# STM32_Rauch_002.net
KiCad netlist of a schematic drawn in EAGLE
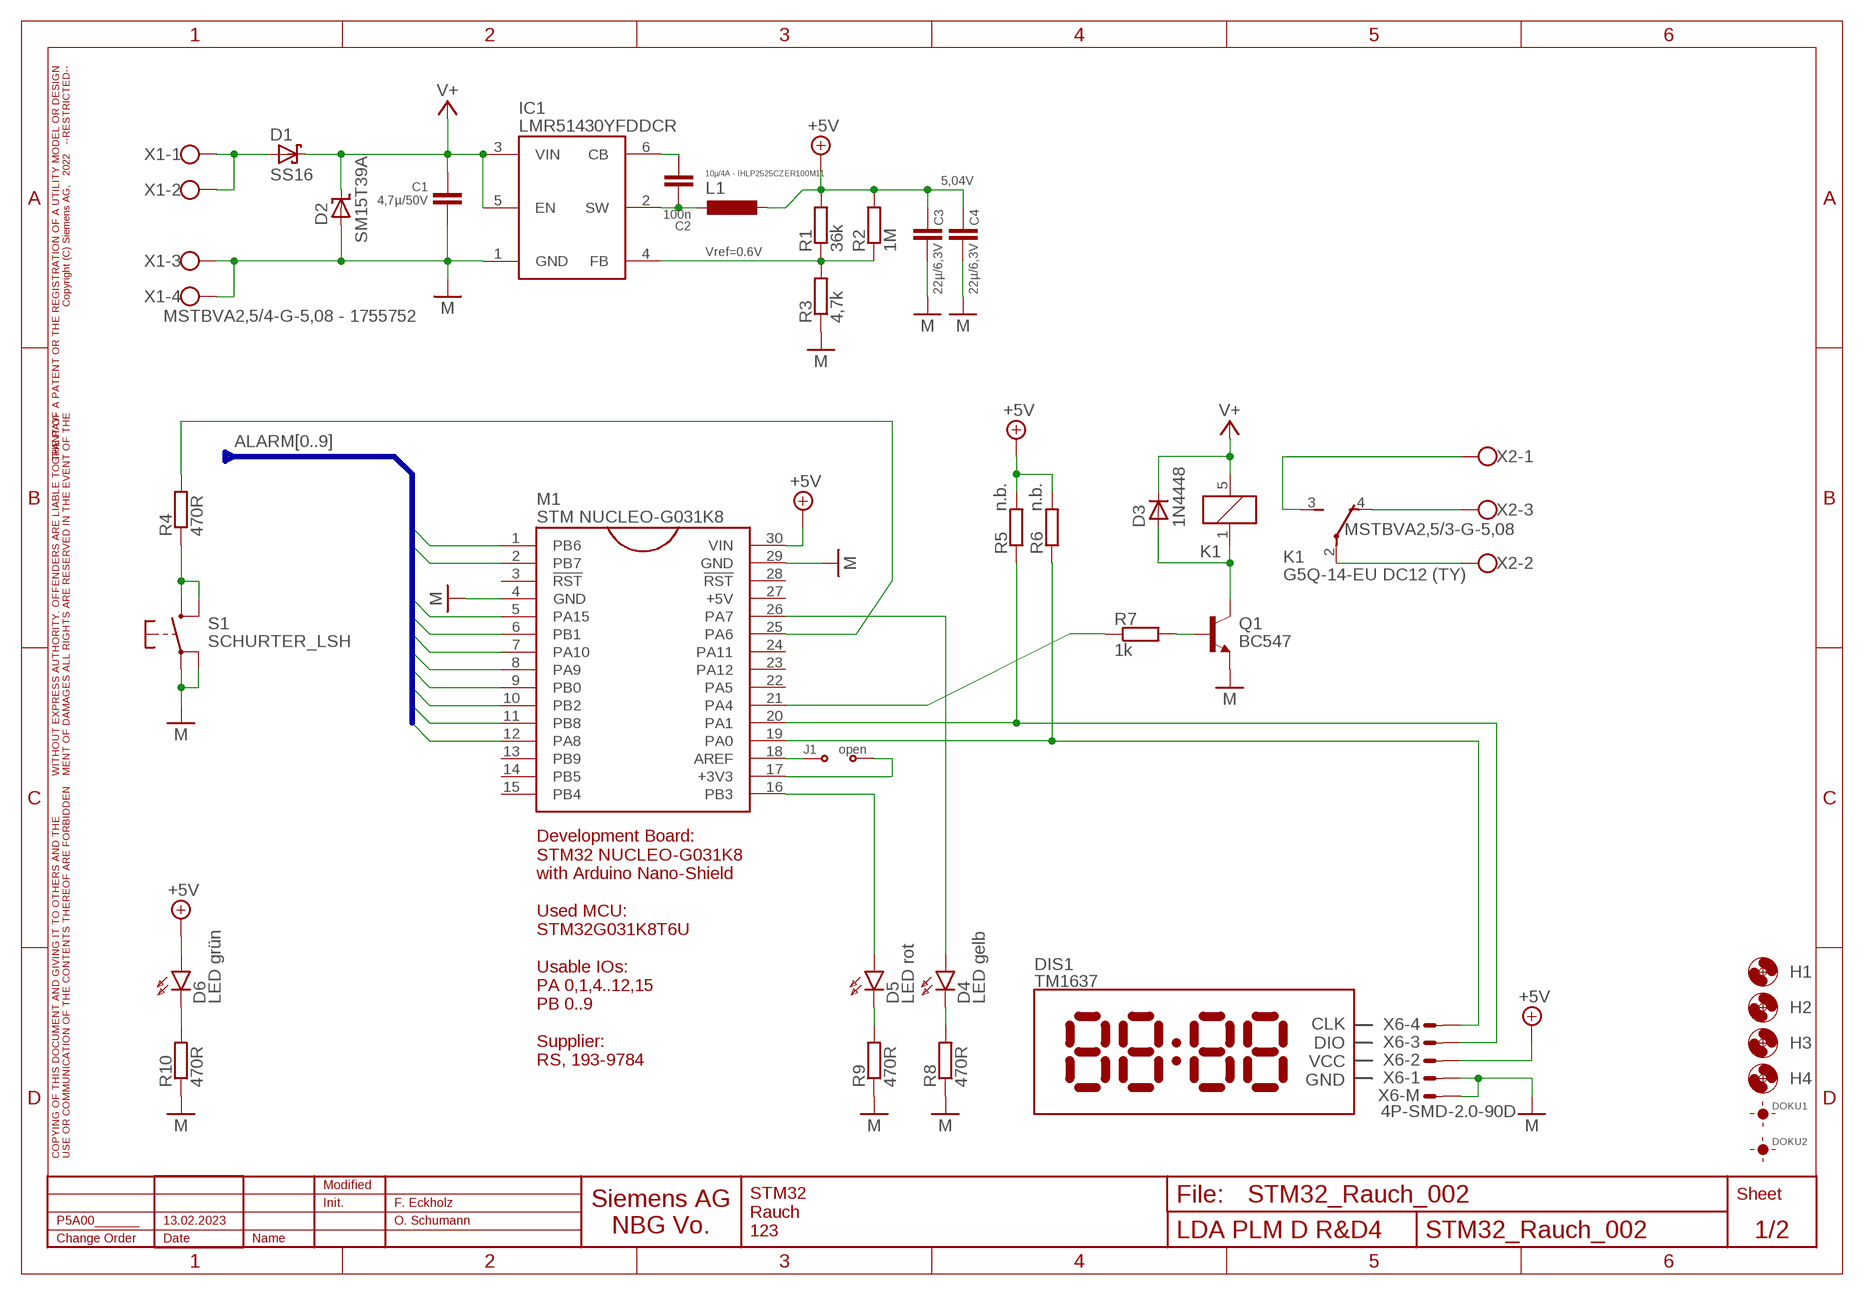
[diagram p0: schematic, sheet 1]
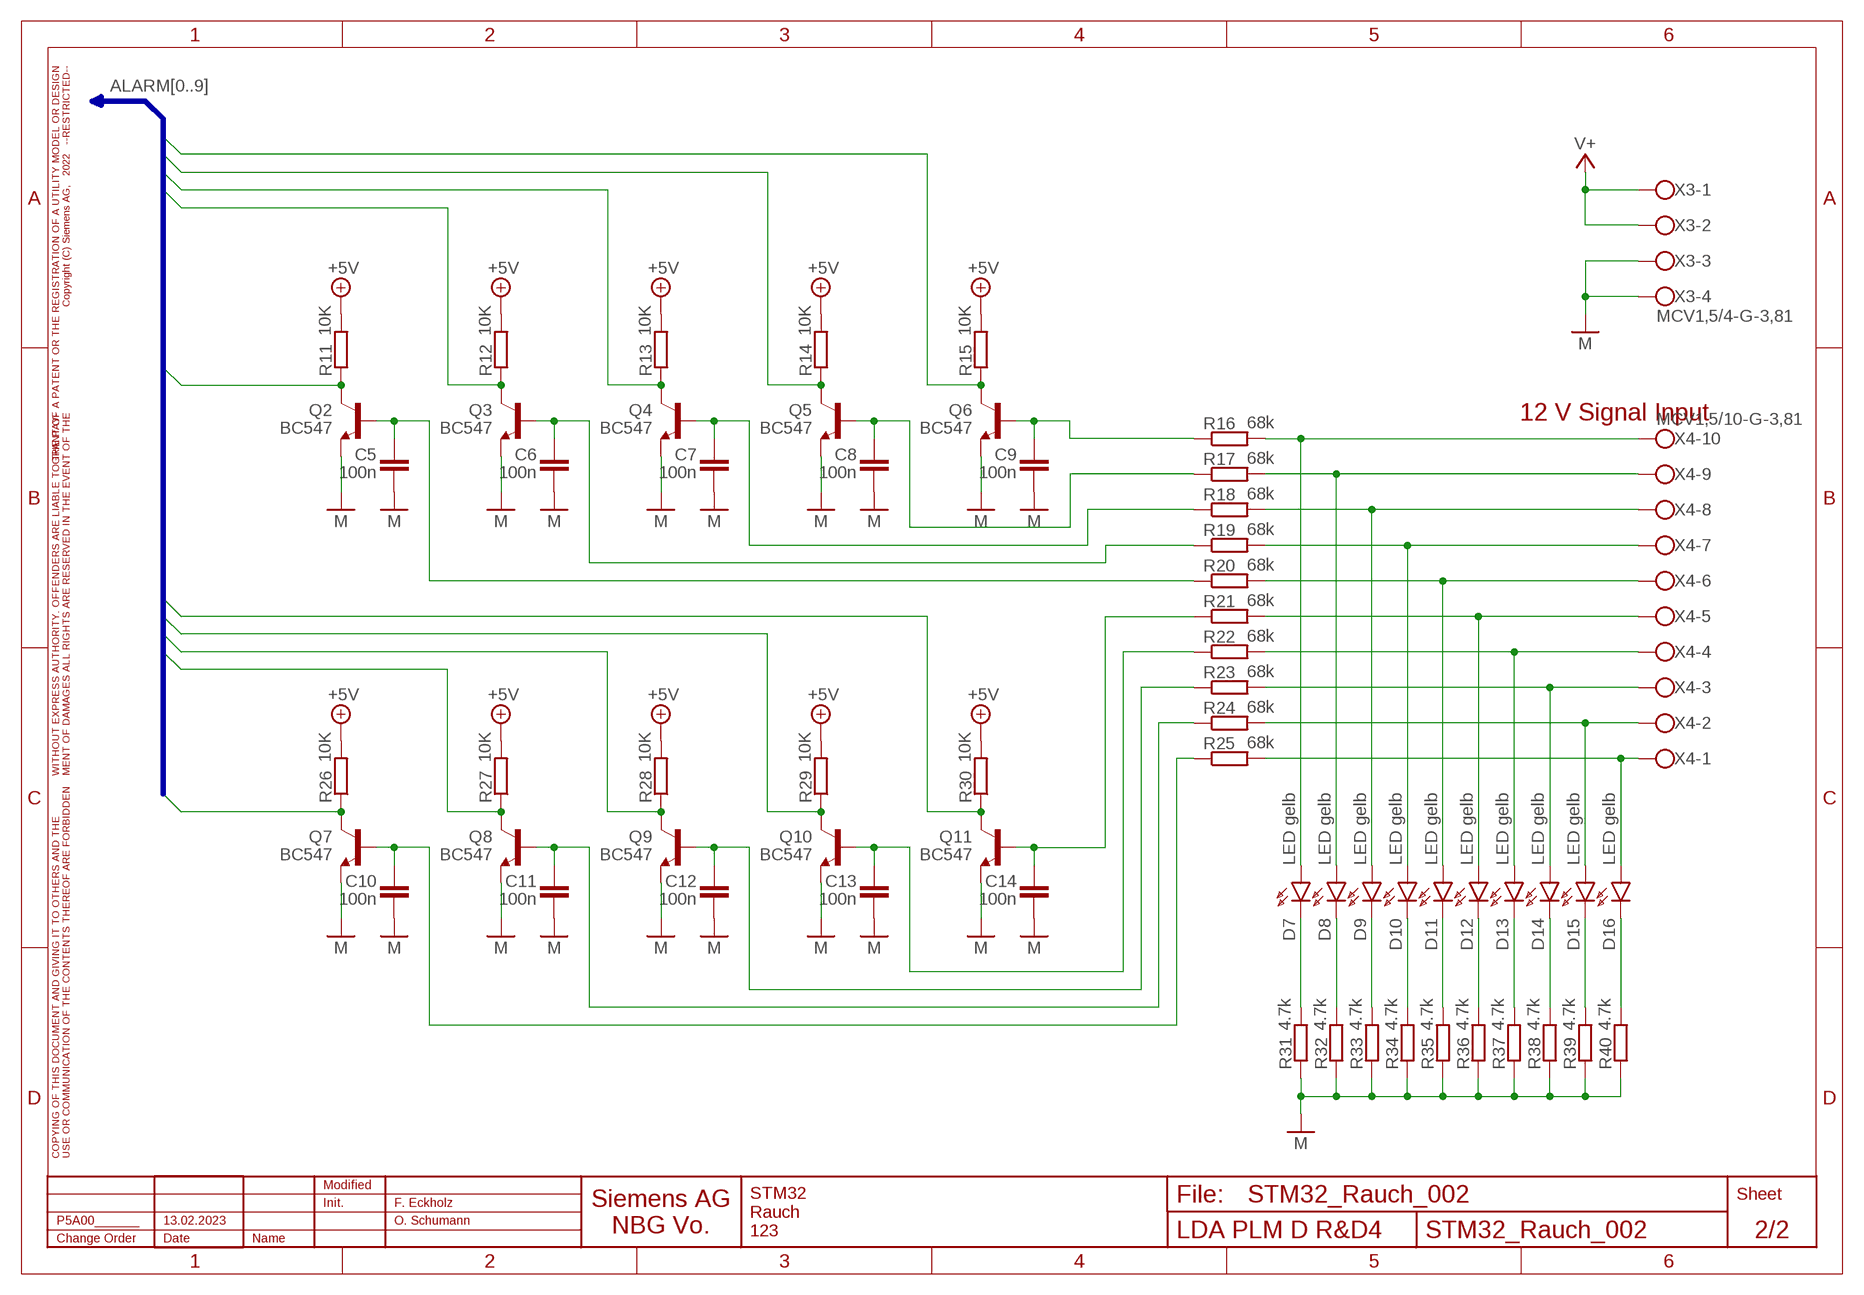
[diagram p1: schematic, sheet 2]

(export (version "E")
  (design (tool "Eeschema 10.0.6"))
  (components
    (comp (ref "C1")
      (value "4,7µ/50V")
      (footprint "eagle-import:CAPC1210")
      (libsource (lib "eagle-import") (part "C-EU1210"))
    )
    (comp (ref "C2")
      (value "100n")
      (footprint "eagle-import:CAPC0603")
      (libsource (lib "eagle-import") (part "C-EU0603"))
    )
    (comp (ref "C3")
      (value "22µ/6,3V")
      (footprint "eagle-import:CAPC1206")
      (libsource (lib "eagle-import") (part "C-EU1206"))
    )
    (comp (ref "C4")
      (value "22µ/6,3V")
      (footprint "eagle-import:CAPC1206")
      (libsource (lib "eagle-import") (part "C-EU1206"))
    )
    (comp (ref "D1")
      (value "SS16")
      (footprint "eagle-import:DIOM-SMA")
      (libsource (lib "eagle-import") (part "DIODE-SCHOTTKY-SMA"))
    )
    (comp (ref "D2")
      (value "SM15T39A")
      (footprint "eagle-import:DIOM-SMC")
      (libsource (lib "eagle-import") (part "DIODE-TVS-UNI-SMC"))
    )
    (comp (ref "D3")
      (value "1N4448")
      (footprint "eagle-import:SOD323")
      (libsource (lib "eagle-import") (part "DIODE-SOD323"))
    )
    (comp (ref "D4")
      (value "LED gelb")
      (footprint "eagle-import:LEDC1608")
      (libsource (lib "eagle-import") (part "DIODE-LED-C1608"))
    )
    (comp (ref "D5")
      (value "LED rot")
      (footprint "eagle-import:LEDC1608")
      (libsource (lib "eagle-import") (part "DIODE-LED-C1608"))
    )
    (comp (ref "D6")
      (value "LED grün")
      (footprint "eagle-import:LEDC1608")
      (libsource (lib "eagle-import") (part "DIODE-LED-C1608"))
    )
    (comp (ref "DIS1")
      (value "TM1637")
      (footprint "eagle-import:TM1637")
      (libsource (lib "eagle-import") (part "TM1637"))
    )
    (comp (ref "DOKU1")
      (value "PAD-FIDU-R200")
      (footprint "eagle-import:FIDU_RUND-2MM")
      (libsource (lib "eagle-import") (part "PAD-FIDU-R200"))
    )
    (comp (ref "DOKU2")
      (value "PAD-FIDU-R200")
      (footprint "eagle-import:FIDU_RUND-2MM")
      (libsource (lib "eagle-import") (part "PAD-FIDU-R200"))
    )
    (comp (ref "DOKU4")
      (value "STM32_Rauch_002")
      (footprint "eagle-import:DOKU-50-TOP")
      (libsource (lib "eagle-import") (part "TEXT-50-TOP"))
    )
    (comp (ref "H1")
      (value "MOUNT-HOLE-3.2")
      (footprint "eagle-import:MOUNT-HOLE-3,2")
      (libsource (lib "eagle-import") (part "MOUNT-HOLE-3.2"))
    )
    (comp (ref "H2")
      (value "MOUNT-HOLE-3.2")
      (footprint "eagle-import:MOUNT-HOLE-3,2")
      (libsource (lib "eagle-import") (part "MOUNT-HOLE-3.2"))
    )
    (comp (ref "H3")
      (value "MOUNT-HOLE-3.2")
      (footprint "eagle-import:MOUNT-HOLE-3,2")
      (libsource (lib "eagle-import") (part "MOUNT-HOLE-3.2"))
    )
    (comp (ref "H4")
      (value "MOUNT-HOLE-3.2")
      (footprint "eagle-import:MOUNT-HOLE-3,2")
      (libsource (lib "eagle-import") (part "MOUNT-HOLE-3.2"))
    )
    (comp (ref "IC1")
      (value "LMR51430YFDDCR")
      (footprint "eagle-import:SOT23-6")
      (libsource (lib "eagle-import") (part "LMR51430"))
    )
    (comp (ref "J1")
      (value "open")
      (footprint "eagle-import:CON-SOLDERJUMPER")
      (libsource (lib "eagle-import") (part "CON-J2D"))
    )
    (comp (ref "K1")
      (value "G5Q-14-EU DC12 (TY)")
      (footprint "eagle-import:OMRON-G5Q")
      (libsource (lib "eagle-import") (part "RELAIS1-OMRON-G5Q"))
    )
    (comp (ref "L1")
      (value "10µ/4A - IHLP2525CZER100M11")
      (footprint "eagle-import:INDM0707")
      (libsource (lib "eagle-import") (part "L-EU0707"))
    )
    (comp (ref "M1")
      (value "STM NUCLEO-G031K8")
      (footprint "eagle-import:NUCLEO32")
      (libsource (lib "eagle-import") (part "STM32-NUCLEO32"))
    )
    (comp (ref "Q1")
      (value "BC547")
      (footprint "eagle-import:SOT23")
      (libsource (lib "eagle-import") (part "TRANSISTOR-NPN-SOT23"))
    )
    (comp (ref "R1")
      (value "36k")
      (footprint "eagle-import:RESC0603")
      (libsource (lib "eagle-import") (part "R-EU_0603"))
    )
    (comp (ref "R2")
      (value "1M")
      (footprint "eagle-import:RESC0603")
      (libsource (lib "eagle-import") (part "R-EU_0603"))
    )
    (comp (ref "R3")
      (value "4,7k")
      (footprint "eagle-import:RESC0603")
      (libsource (lib "eagle-import") (part "R-EU_0603"))
    )
    (comp (ref "R4")
      (value "470R")
      (footprint "eagle-import:RESC0603")
      (libsource (lib "eagle-import") (part "R-EU_0603"))
    )
    (comp (ref "R5")
      (value "n.b.")
      (footprint "eagle-import:RESC0603")
      (libsource (lib "eagle-import") (part "R-EU_0603"))
    )
    (comp (ref "R6")
      (value "n.b.")
      (footprint "eagle-import:RESC0603")
      (libsource (lib "eagle-import") (part "R-EU_0603"))
    )
    (comp (ref "R7")
      (value "1k")
      (footprint "eagle-import:RESC0603")
      (libsource (lib "eagle-import") (part "R-EU_0603"))
    )
    (comp (ref "R8")
      (value "470R")
      (footprint "eagle-import:RESC0603")
      (libsource (lib "eagle-import") (part "R-EU_0603"))
    )
    (comp (ref "R9")
      (value "470R")
      (footprint "eagle-import:RESC0603")
      (libsource (lib "eagle-import") (part "R-EU_0603"))
    )
    (comp (ref "R10")
      (value "470R")
      (footprint "eagle-import:RESC0603")
      (libsource (lib "eagle-import") (part "R-EU_0603"))
    )
    (comp (ref "S1")
      (value "SCHURTER_LSH")
      (footprint "eagle-import:SHURTER_LSH")
      (libsource (lib "eagle-import") (part "SCHURTER_LSH"))
    )
    (comp (ref "X1")
      (value "MSTBVA2,5/4-G-5,08 - 1755752")
      (footprint "eagle-import:MSTBVA2,5_4-G-5,08")
      (libsource (lib "eagle-import") (part "MSTBVA2,5/4-G-5,08"))
    )
    (comp (ref "X2")
      (value "MSTBVA2,5/3-G-5,08")
      (footprint "eagle-import:MSTBVA2,5_3-G-5,08")
      (libsource (lib "eagle-import") (part "MSTBVA2,5/3-G-5,08"))
    )
    (comp (ref "X6")
      (value "4P-SMD-2.0-90D")
      (footprint "eagle-import:4P-SMD-2.0-90D")
      (libsource (lib "eagle-import") (part "4P-SMD-2.0-90D"))
    )
    (comp (ref "C5")
      (value "100n")
      (footprint "eagle-import:CAPC0603")
      (libsource (lib "eagle-import") (part "C-EU0603"))
    )
    (comp (ref "C6")
      (value "100n")
      (footprint "eagle-import:CAPC0603")
      (libsource (lib "eagle-import") (part "C-EU0603"))
    )
    (comp (ref "C7")
      (value "100n")
      (footprint "eagle-import:CAPC0603")
      (libsource (lib "eagle-import") (part "C-EU0603"))
    )
    (comp (ref "C8")
      (value "100n")
      (footprint "eagle-import:CAPC0603")
      (libsource (lib "eagle-import") (part "C-EU0603"))
    )
    (comp (ref "C9")
      (value "100n")
      (footprint "eagle-import:CAPC0603")
      (libsource (lib "eagle-import") (part "C-EU0603"))
    )
    (comp (ref "C10")
      (value "100n")
      (footprint "eagle-import:CAPC0603")
      (libsource (lib "eagle-import") (part "C-EU0603"))
    )
    (comp (ref "C11")
      (value "100n")
      (footprint "eagle-import:CAPC0603")
      (libsource (lib "eagle-import") (part "C-EU0603"))
    )
    (comp (ref "C12")
      (value "100n")
      (footprint "eagle-import:CAPC0603")
      (libsource (lib "eagle-import") (part "C-EU0603"))
    )
    (comp (ref "C13")
      (value "100n")
      (footprint "eagle-import:CAPC0603")
      (libsource (lib "eagle-import") (part "C-EU0603"))
    )
    (comp (ref "C14")
      (value "100n")
      (footprint "eagle-import:CAPC0603")
      (libsource (lib "eagle-import") (part "C-EU0603"))
    )
    (comp (ref "D7")
      (value "LED gelb")
      (footprint "eagle-import:LEDC1608")
      (libsource (lib "eagle-import") (part "DIODE-LED-C1608"))
    )
    (comp (ref "D8")
      (value "LED gelb")
      (footprint "eagle-import:LEDC1608")
      (libsource (lib "eagle-import") (part "DIODE-LED-C1608"))
    )
    (comp (ref "D9")
      (value "LED gelb")
      (footprint "eagle-import:LEDC1608")
      (libsource (lib "eagle-import") (part "DIODE-LED-C1608"))
    )
    (comp (ref "D10")
      (value "LED gelb")
      (footprint "eagle-import:LEDC1608")
      (libsource (lib "eagle-import") (part "DIODE-LED-C1608"))
    )
    (comp (ref "D11")
      (value "LED gelb")
      (footprint "eagle-import:LEDC1608")
      (libsource (lib "eagle-import") (part "DIODE-LED-C1608"))
    )
    (comp (ref "D12")
      (value "LED gelb")
      (footprint "eagle-import:LEDC1608")
      (libsource (lib "eagle-import") (part "DIODE-LED-C1608"))
    )
    (comp (ref "D13")
      (value "LED gelb")
      (footprint "eagle-import:LEDC1608")
      (libsource (lib "eagle-import") (part "DIODE-LED-C1608"))
    )
    (comp (ref "D14")
      (value "LED gelb")
      (footprint "eagle-import:LEDC1608")
      (libsource (lib "eagle-import") (part "DIODE-LED-C1608"))
    )
    (comp (ref "D15")
      (value "LED gelb")
      (footprint "eagle-import:LEDC1608")
      (libsource (lib "eagle-import") (part "DIODE-LED-C1608"))
    )
    (comp (ref "D16")
      (value "LED gelb")
      (footprint "eagle-import:LEDC1608")
      (libsource (lib "eagle-import") (part "DIODE-LED-C1608"))
    )
    (comp (ref "DOKU4")
      (value "STM32_Rauch_002")
      (footprint "eagle-import:DOKU-50-TOP")
      (libsource (lib "eagle-import") (part "TEXT-50-TOP"))
    )
    (comp (ref "Q2")
      (value "BC547")
      (footprint "eagle-import:SOT23")
      (libsource (lib "eagle-import") (part "TRANSISTOR-NPN-SOT23"))
    )
    (comp (ref "Q3")
      (value "BC547")
      (footprint "eagle-import:SOT23")
      (libsource (lib "eagle-import") (part "TRANSISTOR-NPN-SOT23"))
    )
    (comp (ref "Q4")
      (value "BC547")
      (footprint "eagle-import:SOT23")
      (libsource (lib "eagle-import") (part "TRANSISTOR-NPN-SOT23"))
    )
    (comp (ref "Q5")
      (value "BC547")
      (footprint "eagle-import:SOT23")
      (libsource (lib "eagle-import") (part "TRANSISTOR-NPN-SOT23"))
    )
    (comp (ref "Q6")
      (value "BC547")
      (footprint "eagle-import:SOT23")
      (libsource (lib "eagle-import") (part "TRANSISTOR-NPN-SOT23"))
    )
    (comp (ref "Q7")
      (value "BC547")
      (footprint "eagle-import:SOT23")
      (libsource (lib "eagle-import") (part "TRANSISTOR-NPN-SOT23"))
    )
    (comp (ref "Q8")
      (value "BC547")
      (footprint "eagle-import:SOT23")
      (libsource (lib "eagle-import") (part "TRANSISTOR-NPN-SOT23"))
    )
    (comp (ref "Q9")
      (value "BC547")
      (footprint "eagle-import:SOT23")
      (libsource (lib "eagle-import") (part "TRANSISTOR-NPN-SOT23"))
    )
    (comp (ref "Q10")
      (value "BC547")
      (footprint "eagle-import:SOT23")
      (libsource (lib "eagle-import") (part "TRANSISTOR-NPN-SOT23"))
    )
    (comp (ref "Q11")
      (value "BC547")
      (footprint "eagle-import:SOT23")
      (libsource (lib "eagle-import") (part "TRANSISTOR-NPN-SOT23"))
    )
    (comp (ref "R11")
      (value "10K")
      (footprint "eagle-import:RESC0603")
      (libsource (lib "eagle-import") (part "R-EU_0603"))
    )
    (comp (ref "R12")
      (value "10K")
      (footprint "eagle-import:RESC0603")
      (libsource (lib "eagle-import") (part "R-EU_0603"))
    )
    (comp (ref "R13")
      (value "10K")
      (footprint "eagle-import:RESC0603")
      (libsource (lib "eagle-import") (part "R-EU_0603"))
    )
    (comp (ref "R14")
      (value "10K")
      (footprint "eagle-import:RESC0603")
      (libsource (lib "eagle-import") (part "R-EU_0603"))
    )
    (comp (ref "R15")
      (value "10K")
      (footprint "eagle-import:RESC0603")
      (libsource (lib "eagle-import") (part "R-EU_0603"))
    )
    (comp (ref "R16")
      (value "68k")
      (footprint "eagle-import:RESC0603")
      (libsource (lib "eagle-import") (part "R-EU_0603"))
    )
    (comp (ref "R17")
      (value "68k")
      (footprint "eagle-import:RESC0603")
      (libsource (lib "eagle-import") (part "R-EU_0603"))
    )
    (comp (ref "R18")
      (value "68k")
      (footprint "eagle-import:RESC0603")
      (libsource (lib "eagle-import") (part "R-EU_0603"))
    )
    (comp (ref "R19")
      (value "68k")
      (footprint "eagle-import:RESC0603")
      (libsource (lib "eagle-import") (part "R-EU_0603"))
    )
    (comp (ref "R20")
      (value "68k")
      (footprint "eagle-import:RESC0603")
      (libsource (lib "eagle-import") (part "R-EU_0603"))
    )
    (comp (ref "R21")
      (value "68k")
      (footprint "eagle-import:RESC0603")
      (libsource (lib "eagle-import") (part "R-EU_0603"))
    )
    (comp (ref "R22")
      (value "68k")
      (footprint "eagle-import:RESC0603")
      (libsource (lib "eagle-import") (part "R-EU_0603"))
    )
    (comp (ref "R23")
      (value "68k")
      (footprint "eagle-import:RESC0603")
      (libsource (lib "eagle-import") (part "R-EU_0603"))
    )
    (comp (ref "R24")
      (value "68k")
      (footprint "eagle-import:RESC0603")
      (libsource (lib "eagle-import") (part "R-EU_0603"))
    )
    (comp (ref "R25")
      (value "68k")
      (footprint "eagle-import:RESC0603")
      (libsource (lib "eagle-import") (part "R-EU_0603"))
    )
    (comp (ref "R26")
      (value "10K")
      (footprint "eagle-import:RESC0603")
      (libsource (lib "eagle-import") (part "R-EU_0603"))
    )
    (comp (ref "R27")
      (value "10K")
      (footprint "eagle-import:RESC0603")
      (libsource (lib "eagle-import") (part "R-EU_0603"))
    )
    (comp (ref "R28")
      (value "10K")
      (footprint "eagle-import:RESC0603")
      (libsource (lib "eagle-import") (part "R-EU_0603"))
    )
    (comp (ref "R29")
      (value "10K")
      (footprint "eagle-import:RESC0603")
      (libsource (lib "eagle-import") (part "R-EU_0603"))
    )
    (comp (ref "R30")
      (value "10K")
      (footprint "eagle-import:RESC0603")
      (libsource (lib "eagle-import") (part "R-EU_0603"))
    )
    (comp (ref "R31")
      (value "4.7k")
      (footprint "eagle-import:RESC0603")
      (libsource (lib "eagle-import") (part "R-EU_0603"))
    )
    (comp (ref "R32")
      (value "4.7k")
      (footprint "eagle-import:RESC0603")
      (libsource (lib "eagle-import") (part "R-EU_0603"))
    )
    (comp (ref "R33")
      (value "4.7k")
      (footprint "eagle-import:RESC0603")
      (libsource (lib "eagle-import") (part "R-EU_0603"))
    )
    (comp (ref "R34")
      (value "4.7k")
      (footprint "eagle-import:RESC0603")
      (libsource (lib "eagle-import") (part "R-EU_0603"))
    )
    (comp (ref "R35")
      (value "4.7k")
      (footprint "eagle-import:RESC0603")
      (libsource (lib "eagle-import") (part "R-EU_0603"))
    )
    (comp (ref "R36")
      (value "4.7k")
      (footprint "eagle-import:RESC0603")
      (libsource (lib "eagle-import") (part "R-EU_0603"))
    )
    (comp (ref "R37")
      (value "4.7k")
      (footprint "eagle-import:RESC0603")
      (libsource (lib "eagle-import") (part "R-EU_0603"))
    )
    (comp (ref "R38")
      (value "4.7k")
      (footprint "eagle-import:RESC0603")
      (libsource (lib "eagle-import") (part "R-EU_0603"))
    )
    (comp (ref "R39")
      (value "4.7k")
      (footprint "eagle-import:RESC0603")
      (libsource (lib "eagle-import") (part "R-EU_0603"))
    )
    (comp (ref "R40")
      (value "4.7k")
      (footprint "eagle-import:RESC0603")
      (libsource (lib "eagle-import") (part "R-EU_0603"))
    )
    (comp (ref "X3")
      (value "MCV1,5/4-G-3,81")
      (footprint "eagle-import:MCV1,5_4-G-3,81")
      (libsource (lib "eagle-import") (part "MCV1,5/4-G-3,81"))
    )
    (comp (ref "X4")
      (value "MCV1,5/10-G-3,81")
      (footprint "eagle-import:MCV1,5_10-G-3,81")
      (libsource (lib "eagle-import") (part "MCV1,5/10-G-3,81"))
    )
  )
  (nets
    (net (code "1") (name "+5V") (class "Default")
      (node (ref "C3") (pin "2") (pinfunction "2_2") (pintype "passive"))
      (node (ref "C4") (pin "2") (pinfunction "2_2") (pintype "passive"))
      (node (ref "D6") (pin "2") (pinfunction "A_2") (pintype "passive"))
      (node (ref "L1") (pin "2") (pinfunction "2_2") (pintype "passive"))
      (node (ref "M1") (pin "30") (pinfunction "VIN_30") (pintype "passive"))
      (node (ref "R1") (pin "2") (pinfunction "2_2") (pintype "passive"))
      (node (ref "R11") (pin "2") (pinfunction "2_2") (pintype "passive"))
      (node (ref "R12") (pin "2") (pinfunction "2_2") (pintype "passive"))
      (node (ref "R13") (pin "2") (pinfunction "2_2") (pintype "passive"))
      (node (ref "R14") (pin "2") (pinfunction "2_2") (pintype "passive"))
      (node (ref "R15") (pin "2") (pinfunction "2_2") (pintype "passive"))
      (node (ref "R2") (pin "2") (pinfunction "2_2") (pintype "passive"))
      (node (ref "R26") (pin "2") (pinfunction "2_2") (pintype "passive"))
      (node (ref "R27") (pin "2") (pinfunction "2_2") (pintype "passive"))
      (node (ref "R28") (pin "2") (pinfunction "2_2") (pintype "passive"))
      (node (ref "R29") (pin "2") (pinfunction "2_2") (pintype "passive"))
      (node (ref "R30") (pin "2") (pinfunction "2_2") (pintype "passive"))
      (node (ref "R5") (pin "2") (pinfunction "2_2") (pintype "passive"))
      (node (ref "R6") (pin "2") (pinfunction "2_2") (pintype "passive"))
      (node (ref "X6") (pin "2") (pinfunction "S_2") (pintype "passive"))
    )
    (net (code "4") (name "ALARM0") (class "Default")
      (node (ref "M1") (pin "1") (pinfunction "PB6_1") (pintype "bidirectional"))
      (node (ref "Q6") (pin "3") (pinfunction "C_3") (pintype "passive"))
      (node (ref "R15") (pin "1") (pinfunction "1_1") (pintype "passive"))
    )
    (net (code "5") (name "ALARM1") (class "Default")
      (node (ref "M1") (pin "2") (pinfunction "PB7_2") (pintype "bidirectional"))
      (node (ref "Q5") (pin "3") (pinfunction "C_3") (pintype "passive"))
      (node (ref "R14") (pin "1") (pinfunction "1_1") (pintype "passive"))
    )
    (net (code "6") (name "ALARM2") (class "Default")
      (node (ref "M1") (pin "5") (pinfunction "PA15_5") (pintype "bidirectional"))
      (node (ref "Q4") (pin "3") (pinfunction "C_3") (pintype "passive"))
      (node (ref "R13") (pin "1") (pinfunction "1_1") (pintype "passive"))
    )
    (net (code "7") (name "ALARM3") (class "Default")
      (node (ref "M1") (pin "6") (pinfunction "PB1_6") (pintype "bidirectional"))
      (node (ref "Q3") (pin "3") (pinfunction "C_3") (pintype "passive"))
      (node (ref "R12") (pin "1") (pinfunction "1_1") (pintype "passive"))
    )
    (net (code "8") (name "ALARM4") (class "Default")
      (node (ref "M1") (pin "7") (pinfunction "PA10_7") (pintype "bidirectional"))
      (node (ref "Q2") (pin "3") (pinfunction "C_3") (pintype "passive"))
      (node (ref "R11") (pin "1") (pinfunction "1_1") (pintype "passive"))
    )
    (net (code "9") (name "ALARM5") (class "Default")
      (node (ref "M1") (pin "8") (pinfunction "PA9_8") (pintype "bidirectional"))
      (node (ref "Q11") (pin "3") (pinfunction "C_3") (pintype "passive"))
      (node (ref "R30") (pin "1") (pinfunction "1_1") (pintype "passive"))
    )
    (net (code "10") (name "ALARM6") (class "Default")
      (node (ref "M1") (pin "9") (pinfunction "PB0_9") (pintype "bidirectional"))
      (node (ref "Q10") (pin "3") (pinfunction "C_3") (pintype "passive"))
      (node (ref "R29") (pin "1") (pinfunction "1_1") (pintype "passive"))
    )
    (net (code "11") (name "ALARM7") (class "Default")
      (node (ref "M1") (pin "10") (pinfunction "PB2_10") (pintype "bidirectional"))
      (node (ref "Q9") (pin "3") (pinfunction "C_3") (pintype "passive"))
      (node (ref "R28") (pin "1") (pinfunction "1_1") (pintype "passive"))
    )
    (net (code "12") (name "ALARM8") (class "Default")
      (node (ref "M1") (pin "11") (pinfunction "PB8_11") (pintype "bidirectional"))
      (node (ref "Q8") (pin "3") (pinfunction "C_3") (pintype "passive"))
      (node (ref "R27") (pin "1") (pinfunction "1_1") (pintype "passive"))
    )
    (net (code "13") (name "ALARM9") (class "Default")
      (node (ref "M1") (pin "12") (pinfunction "PA8_12") (pintype "bidirectional"))
      (node (ref "Q7") (pin "3") (pinfunction "C_3") (pintype "passive"))
      (node (ref "R26") (pin "1") (pinfunction "1_1") (pintype "passive"))
    )
    (net (code "14") (name "M") (class "Default")
      (node (ref "C1") (pin "1") (pinfunction "1_1") (pintype "passive"))
      (node (ref "C10") (pin "1") (pinfunction "1_1") (pintype "passive"))
      (node (ref "C11") (pin "1") (pinfunction "1_1") (pintype "passive"))
      (node (ref "C12") (pin "1") (pinfunction "1_1") (pintype "passive"))
      (node (ref "C13") (pin "1") (pinfunction "1_1") (pintype "passive"))
      (node (ref "C14") (pin "1") (pinfunction "1_1") (pintype "passive"))
      (node (ref "C3") (pin "1") (pinfunction "1_1") (pintype "passive"))
      (node (ref "C4") (pin "1") (pinfunction "1_1") (pintype "passive"))
      (node (ref "C5") (pin "1") (pinfunction "1_1") (pintype "passive"))
      (node (ref "C6") (pin "1") (pinfunction "1_1") (pintype "passive"))
      (node (ref "C7") (pin "1") (pinfunction "1_1") (pintype "passive"))
      (node (ref "C8") (pin "1") (pinfunction "1_1") (pintype "passive"))
      (node (ref "C9") (pin "1") (pinfunction "1_1") (pintype "passive"))
      (node (ref "D2") (pin "2") (pinfunction "A_2") (pintype "passive"))
      (node (ref "IC1") (pin "1") (pinfunction "GND_1") (pintype "power_in"))
      (node (ref "M1") (pin "29") (pinfunction "GND_29") (pintype "passive"))
      (node (ref "M1") (pin "4") (pinfunction "GND_4") (pintype "passive"))
      (node (ref "Q1") (pin "2") (pinfunction "E_2") (pintype "passive"))
      (node (ref "Q10") (pin "2") (pinfunction "E_2") (pintype "passive"))
      (node (ref "Q11") (pin "2") (pinfunction "E_2") (pintype "passive"))
      (node (ref "Q2") (pin "2") (pinfunction "E_2") (pintype "passive"))
      (node (ref "Q3") (pin "2") (pinfunction "E_2") (pintype "passive"))
      (node (ref "Q4") (pin "2") (pinfunction "E_2") (pintype "passive"))
      (node (ref "Q5") (pin "2") (pinfunction "E_2") (pintype "passive"))
      (node (ref "Q6") (pin "2") (pinfunction "E_2") (pintype "passive"))
      (node (ref "Q7") (pin "2") (pinfunction "E_2") (pintype "passive"))
      (node (ref "Q8") (pin "2") (pinfunction "E_2") (pintype "passive"))
      (node (ref "Q9") (pin "2") (pinfunction "E_2") (pintype "passive"))
      (node (ref "R10") (pin "1") (pinfunction "1_1") (pintype "passive"))
      (node (ref "R3") (pin "1") (pinfunction "1_1") (pintype "passive"))
      (node (ref "R31") (pin "1") (pinfunction "1_1") (pintype "passive"))
      (node (ref "R32") (pin "1") (pinfunction "1_1") (pintype "passive"))
      (node (ref "R33") (pin "1") (pinfunction "1_1") (pintype "passive"))
      (node (ref "R34") (pin "1") (pinfunction "1_1") (pintype "passive"))
      (node (ref "R35") (pin "1") (pinfunction "1_1") (pintype "passive"))
      (node (ref "R36") (pin "1") (pinfunction "1_1") (pintype "passive"))
      (node (ref "R37") (pin "1") (pinfunction "1_1") (pintype "passive"))
      (node (ref "R38") (pin "1") (pinfunction "1_1") (pintype "passive"))
      (node (ref "R39") (pin "1") (pinfunction "1_1") (pintype "passive"))
      (node (ref "R40") (pin "1") (pinfunction "1_1") (pintype "passive"))
      (node (ref "R8") (pin "1") (pinfunction "1_1") (pintype "passive"))
      (node (ref "R9") (pin "1") (pinfunction "1_1") (pintype "passive"))
      (node (ref "S1") (pin "1") (pinfunction "P_1") (pintype "passive"))
      (node (ref "S1") (pin "2") (pinfunction "P_2") (pintype "passive"))
      (node (ref "X1") (pin "3") (pinfunction "KL_3") (pintype "passive"))
      (node (ref "X1") (pin "4") (pinfunction "KL_4") (pintype "passive"))
      (node (ref "X3") (pin "P$3") (pinfunction "KL_P$3") (pintype "passive"))
      (node (ref "X3") (pin "P$4") (pinfunction "KL_P$4") (pintype "passive"))
      (node (ref "X6") (pin "1") (pinfunction "S_1") (pintype "passive"))
      (node (ref "X6") (pin "SS1") (pinfunction "S_SS1") (pintype "passive"))
      (node (ref "X6") (pin "SS2") (pinfunction "S_SS2") (pintype "passive"))
    )
    (net (code "15") (name "Net-(D1-A)") (class "Default")
      (node (ref "D1") (pin "2") (pinfunction "A_2") (pintype "passive"))
      (node (ref "X1") (pin "1") (pinfunction "KL_1") (pintype "passive"))
      (node (ref "X1") (pin "2") (pinfunction "KL_2") (pintype "passive"))
    )
    (net (code "16") (name "Net-(D4-A)") (class "Default")
      (node (ref "D4") (pin "2") (pinfunction "A_2") (pintype "passive"))
      (node (ref "M1") (pin "26") (pinfunction "PA7_26") (pintype "bidirectional"))
    )
    (net (code "17") (name "Net-(D4-C)") (class "Default")
      (node (ref "D4") (pin "1") (pinfunction "C_1") (pintype "passive"))
      (node (ref "R8") (pin "2") (pinfunction "2_2") (pintype "passive"))
    )
    (net (code "18") (name "Net-(D5-A)") (class "Default")
      (node (ref "D5") (pin "2") (pinfunction "A_2") (pintype "passive"))
      (node (ref "M1") (pin "16") (pinfunction "PB3_16") (pintype "bidirectional"))
    )
    (net (code "19") (name "Net-(D5-C)") (class "Default")
      (node (ref "D5") (pin "1") (pinfunction "C_1") (pintype "passive"))
      (node (ref "R9") (pin "2") (pinfunction "2_2") (pintype "passive"))
    )
    (net (code "20") (name "Net-(D6-C)") (class "Default")
      (node (ref "D6") (pin "1") (pinfunction "C_1") (pintype "passive"))
      (node (ref "R10") (pin "2") (pinfunction "2_2") (pintype "passive"))
    )
    (net (code "21") (name "Net-(D7-A)") (class "Default")
      (node (ref "D7") (pin "2") (pinfunction "A_2") (pintype "passive"))
      (node (ref "R16") (pin "2") (pinfunction "2_2") (pintype "passive"))
      (node (ref "X4") (pin "P$10") (pinfunction "KL_P$10") (pintype "passive"))
    )
    (net (code "22") (name "Net-(D7-C)") (class "Default")
      (node (ref "D7") (pin "1") (pinfunction "C_1") (pintype "passive"))
      (node (ref "R31") (pin "2") (pinfunction "2_2") (pintype "passive"))
    )
    (net (code "23") (name "Net-(D8-A)") (class "Default")
      (node (ref "D8") (pin "2") (pinfunction "A_2") (pintype "passive"))
      (node (ref "R17") (pin "2") (pinfunction "2_2") (pintype "passive"))
      (node (ref "X4") (pin "P$9") (pinfunction "KL_P$9") (pintype "passive"))
    )
    (net (code "24") (name "Net-(D8-C)") (class "Default")
      (node (ref "D8") (pin "1") (pinfunction "C_1") (pintype "passive"))
      (node (ref "R32") (pin "2") (pinfunction "2_2") (pintype "passive"))
    )
    (net (code "25") (name "Net-(D9-A)") (class "Default")
      (node (ref "D9") (pin "2") (pinfunction "A_2") (pintype "passive"))
      (node (ref "R18") (pin "2") (pinfunction "2_2") (pintype "passive"))
      (node (ref "X4") (pin "P$8") (pinfunction "KL_P$8") (pintype "passive"))
    )
    (net (code "26") (name "Net-(D9-C)") (class "Default")
      (node (ref "D9") (pin "1") (pinfunction "C_1") (pintype "passive"))
      (node (ref "R33") (pin "2") (pinfunction "2_2") (pintype "passive"))
    )
    (net (code "27") (name "Net-(D10-A)") (class "Default")
      (node (ref "D10") (pin "2") (pinfunction "A_2") (pintype "passive"))
      (node (ref "R19") (pin "2") (pinfunction "2_2") (pintype "passive"))
      (node (ref "X4") (pin "P$7") (pinfunction "KL_P$7") (pintype "passive"))
    )
    (net (code "28") (name "Net-(D10-C)") (class "Default")
      (node (ref "D10") (pin "1") (pinfunction "C_1") (pintype "passive"))
      (node (ref "R34") (pin "2") (pinfunction "2_2") (pintype "passive"))
    )
    (net (code "29") (name "Net-(D11-A)") (class "Default")
      (node (ref "D11") (pin "2") (pinfunction "A_2") (pintype "passive"))
      (node (ref "R20") (pin "2") (pinfunction "2_2") (pintype "passive"))
      (node (ref "X4") (pin "P$6") (pinfunction "KL_P$6") (pintype "passive"))
    )
    (net (code "30") (name "Net-(D11-C)") (class "Default")
      (node (ref "D11") (pin "1") (pinfunction "C_1") (pintype "passive"))
      (node (ref "R35") (pin "2") (pinfunction "2_2") (pintype "passive"))
    )
    (net (code "31") (name "Net-(D12-A)") (class "Default")
      (node (ref "D12") (pin "2") (pinfunction "A_2") (pintype "passive"))
      (node (ref "R21") (pin "2") (pinfunction "2_2") (pintype "passive"))
      (node (ref "X4") (pin "P$5") (pinfunction "KL_P$5") (pintype "passive"))
    )
    (net (code "32") (name "Net-(D12-C)") (class "Default")
      (node (ref "D12") (pin "1") (pinfunction "C_1") (pintype "passive"))
      (node (ref "R36") (pin "2") (pinfunction "2_2") (pintype "passive"))
    )
    (net (code "33") (name "Net-(D13-A)") (class "Default")
      (node (ref "D13") (pin "2") (pinfunction "A_2") (pintype "passive"))
      (node (ref "R22") (pin "2") (pinfunction "2_2") (pintype "passive"))
      (node (ref "X4") (pin "P$4") (pinfunction "KL_P$4") (pintype "passive"))
    )
    (net (code "34") (name "Net-(D13-C)") (class "Default")
      (node (ref "D13") (pin "1") (pinfunction "C_1") (pintype "passive"))
      (node (ref "R37") (pin "2") (pinfunction "2_2") (pintype "passive"))
    )
    (net (code "35") (name "Net-(D14-A)") (class "Default")
      (node (ref "D14") (pin "2") (pinfunction "A_2") (pintype "passive"))
      (node (ref "R23") (pin "2") (pinfunction "2_2") (pintype "passive"))
      (node (ref "X4") (pin "P$3") (pinfunction "KL_P$3") (pintype "passive"))
    )
    (net (code "36") (name "Net-(D14-C)") (class "Default")
      (node (ref "D14") (pin "1") (pinfunction "C_1") (pintype "passive"))
      (node (ref "R38") (pin "2") (pinfunction "2_2") (pintype "passive"))
    )
    (net (code "37") (name "Net-(D15-A)") (class "Default")
      (node (ref "D15") (pin "2") (pinfunction "A_2") (pintype "passive"))
      (node (ref "R24") (pin "2") (pinfunction "2_2") (pintype "passive"))
      (node (ref "X4") (pin "P$2") (pinfunction "KL_P$2") (pintype "passive"))
    )
    (net (code "38") (name "Net-(D15-C)") (class "Default")
      (node (ref "D15") (pin "1") (pinfunction "C_1") (pintype "passive"))
      (node (ref "R39") (pin "2") (pinfunction "2_2") (pintype "passive"))
    )
    (net (code "39") (name "Net-(D16-A)") (class "Default")
      (node (ref "D16") (pin "2") (pinfunction "A_2") (pintype "passive"))
      (node (ref "R25") (pin "2") (pinfunction "2_2") (pintype "passive"))
      (node (ref "X4") (pin "P$1") (pinfunction "KL_P$1") (pintype "passive"))
    )
    (net (code "40") (name "Net-(D16-C)") (class "Default")
      (node (ref "D16") (pin "1") (pinfunction "C_1") (pintype "passive"))
      (node (ref "R40") (pin "2") (pinfunction "2_2") (pintype "passive"))
    )
    (net (code "41") (name "Net-(IC1-CB)") (class "Default")
      (node (ref "C2") (pin "1") (pinfunction "1_1") (pintype "passive"))
      (node (ref "IC1") (pin "6") (pinfunction "CB_6") (pintype "input"))
    )
    (net (code "42") (name "Net-(IC1-FB)") (class "Default")
      (node (ref "IC1") (pin "4") (pinfunction "FB_4") (pintype "input"))
      (node (ref "R1") (pin "1") (pinfunction "1_1") (pintype "passive"))
      (node (ref "R2") (pin "1") (pinfunction "1_1") (pintype "passive"))
      (node (ref "R3") (pin "2") (pinfunction "2_2") (pintype "passive"))
    )
    (net (code "43") (name "Net-(IC1-SW)") (class "Default")
      (node (ref "C2") (pin "2") (pinfunction "2_2") (pintype "passive"))
      (node (ref "IC1") (pin "2") (pinfunction "SW_2") (pintype "output"))
      (node (ref "L1") (pin "1") (pinfunction "1_1") (pintype "passive"))
    )
    (net (code "44") (name "Net-(K1A-COIL1)") (class "Default")
      (node (ref "D3") (pin "A") (pinfunction "A_A") (pintype "passive"))
      (node (ref "K1") (pin "1") (pinfunction "COIL1_1") (pintype "passive"))
      (node (ref "Q1") (pin "3") (pinfunction "C_3") (pintype "passive"))
    )
    (net (code "45") (name "Net-(K1B-C)") (class "Default")
      (node (ref "K1") (pin "2") (pinfunction "C_2") (pintype "passive"))
      (node (ref "X2") (pin "2") (pinfunction "KL_2") (pintype "passive"))
    )
    (net (code "46") (name "Net-(K1B-NC)") (class "Default")
      (node (ref "K1") (pin "4") (pinfunction "NC_4") (pintype "passive"))
      (node (ref "X2") (pin "3") (pinfunction "KL_3") (pintype "passive"))
    )
    (net (code "47") (name "Net-(K1B-NO)") (class "Default")
      (node (ref "K1") (pin "3") (pinfunction "NO_3") (pintype "passive"))
      (node (ref "X2") (pin "1") (pinfunction "KL_1") (pintype "passive"))
    )
    (net (code "48") (name "Net-(M1-+3V3)") (class "Default")
      (node (ref "J1") (pin "2") (pinfunction "2_2") (pintype "bidirectional"))
      (node (ref "M1") (pin "17") (pinfunction "+3V3_17") (pintype "passive"))
    )
    (net (code "49") (name "Net-(M1-AREF)") (class "Default")
      (node (ref "J1") (pin "1") (pinfunction "1_1") (pintype "bidirectional"))
      (node (ref "M1") (pin "18") (pinfunction "AREF_18") (pintype "passive"))
    )
    (net (code "50") (name "Net-(M1-PA0)") (class "Default")
      (node (ref "M1") (pin "19") (pinfunction "PA0_19") (pintype "bidirectional"))
      (node (ref "R6") (pin "1") (pinfunction "1_1") (pintype "passive"))
      (node (ref "X6") (pin "4") (pinfunction "S_4") (pintype "passive"))
    )
    (net (code "51") (name "Net-(M1-PA1)") (class "Default")
      (node (ref "M1") (pin "20") (pinfunction "PA1_20") (pintype "bidirectional"))
      (node (ref "R5") (pin "1") (pinfunction "1_1") (pintype "passive"))
      (node (ref "X6") (pin "3") (pinfunction "S_3") (pintype "passive"))
    )
    (net (code "52") (name "Net-(M1-PA4)") (class "Default")
      (node (ref "M1") (pin "21") (pinfunction "PA4_21") (pintype "bidirectional"))
      (node (ref "R7") (pin "1") (pinfunction "1_1") (pintype "passive"))
    )
    (net (code "53") (name "Net-(M1-PA6)") (class "Default")
      (node (ref "M1") (pin "25") (pinfunction "PA6_25") (pintype "bidirectional"))
      (node (ref "R4") (pin "2") (pinfunction "2_2") (pintype "passive"))
    )
    (net (code "54") (name "Net-(Q1-B)") (class "Default")
      (node (ref "Q1") (pin "1") (pinfunction "B_1") (pintype "passive"))
      (node (ref "R7") (pin "2") (pinfunction "2_2") (pintype "passive"))
    )
    (net (code "55") (name "Net-(Q2-B)") (class "Default")
      (node (ref "C5") (pin "2") (pinfunction "2_2") (pintype "passive"))
      (node (ref "Q2") (pin "1") (pinfunction "B_1") (pintype "passive"))
      (node (ref "R20") (pin "1") (pinfunction "1_1") (pintype "passive"))
    )
    (net (code "56") (name "Net-(Q3-B)") (class "Default")
      (node (ref "C6") (pin "2") (pinfunction "2_2") (pintype "passive"))
      (node (ref "Q3") (pin "1") (pinfunction "B_1") (pintype "passive"))
      (node (ref "R19") (pin "1") (pinfunction "1_1") (pintype "passive"))
    )
    (net (code "57") (name "Net-(Q4-B)") (class "Default")
      (node (ref "C7") (pin "2") (pinfunction "2_2") (pintype "passive"))
      (node (ref "Q4") (pin "1") (pinfunction "B_1") (pintype "passive"))
      (node (ref "R18") (pin "1") (pinfunction "1_1") (pintype "passive"))
    )
    (net (code "58") (name "Net-(Q5-B)") (class "Default")
      (node (ref "C8") (pin "2") (pinfunction "2_2") (pintype "passive"))
      (node (ref "Q5") (pin "1") (pinfunction "B_1") (pintype "passive"))
      (node (ref "R17") (pin "1") (pinfunction "1_1") (pintype "passive"))
    )
    (net (code "59") (name "Net-(Q6-B)") (class "Default")
      (node (ref "C9") (pin "2") (pinfunction "2_2") (pintype "passive"))
      (node (ref "Q6") (pin "1") (pinfunction "B_1") (pintype "passive"))
      (node (ref "R16") (pin "1") (pinfunction "1_1") (pintype "passive"))
    )
    (net (code "60") (name "Net-(Q7-B)") (class "Default")
      (node (ref "C10") (pin "2") (pinfunction "2_2") (pintype "passive"))
      (node (ref "Q7") (pin "1") (pinfunction "B_1") (pintype "passive"))
      (node (ref "R25") (pin "1") (pinfunction "1_1") (pintype "passive"))
    )
    (net (code "61") (name "Net-(Q8-B)") (class "Default")
      (node (ref "C11") (pin "2") (pinfunction "2_2") (pintype "passive"))
      (node (ref "Q8") (pin "1") (pinfunction "B_1") (pintype "passive"))
      (node (ref "R24") (pin "1") (pinfunction "1_1") (pintype "passive"))
    )
    (net (code "62") (name "Net-(Q9-B)") (class "Default")
      (node (ref "C12") (pin "2") (pinfunction "2_2") (pintype "passive"))
      (node (ref "Q9") (pin "1") (pinfunction "B_1") (pintype "passive"))
      (node (ref "R23") (pin "1") (pinfunction "1_1") (pintype "passive"))
    )
    (net (code "63") (name "Net-(Q10-B)") (class "Default")
      (node (ref "C13") (pin "2") (pinfunction "2_2") (pintype "passive"))
      (node (ref "Q10") (pin "1") (pinfunction "B_1") (pintype "passive"))
      (node (ref "R22") (pin "1") (pinfunction "1_1") (pintype "passive"))
    )
    (net (code "64") (name "Net-(Q11-B)") (class "Default")
      (node (ref "C14") (pin "2") (pinfunction "2_2") (pintype "passive"))
      (node (ref "Q11") (pin "1") (pinfunction "B_1") (pintype "passive"))
      (node (ref "R21") (pin "1") (pinfunction "1_1") (pintype "passive"))
    )
    (net (code "65") (name "Net-(R4-Pad1)") (class "Default")
      (node (ref "R4") (pin "1") (pinfunction "1_1") (pintype "passive"))
      (node (ref "S1") (pin "3") (pinfunction "S_3") (pintype "passive"))
      (node (ref "S1") (pin "4") (pinfunction "S_4") (pintype "passive"))
    )
    (net (code "66") (name "V+") (class "Default")
      (node (ref "C1") (pin "2") (pinfunction "2_2") (pintype "passive"))
      (node (ref "D1") (pin "1") (pinfunction "K_1") (pintype "passive"))
      (node (ref "D2") (pin "1") (pinfunction "C_1") (pintype "passive"))
      (node (ref "D3") (pin "C") (pinfunction "C_C") (pintype "passive"))
      (node (ref "IC1") (pin "3") (pinfunction "VIN_3") (pintype "power_in"))
      (node (ref "IC1") (pin "5") (pinfunction "EN_5") (pintype "input"))
      (node (ref "K1") (pin "5") (pinfunction "COIL2_5") (pintype "passive"))
      (node (ref "X3") (pin "P$1") (pinfunction "KL_P$1") (pintype "passive"))
      (node (ref "X3") (pin "P$2") (pinfunction "KL_P$2") (pintype "passive"))
    )
    (net (code "67") (name "unconnected-(M1-+5V-Pad27)") (class "Default")
      (node (ref "M1") (pin "27") (pinfunction "+5V_27") (pintype "passive"))
    )
    (net (code "68") (name "unconnected-(M1-PA5-Pad22)") (class "Default")
      (node (ref "M1") (pin "22") (pinfunction "PA5_22") (pintype "bidirectional"))
    )
    (net (code "69") (name "unconnected-(M1-PA11-Pad24)") (class "Default")
      (node (ref "M1") (pin "24") (pinfunction "PA11_24") (pintype "bidirectional"))
    )
    (net (code "70") (name "unconnected-(M1-PA12-Pad23)") (class "Default")
      (node (ref "M1") (pin "23") (pinfunction "PA12_23") (pintype "bidirectional"))
    )
    (net (code "71") (name "unconnected-(M1-PB4-Pad15)") (class "Default")
      (node (ref "M1") (pin "15") (pinfunction "PB4_15") (pintype "bidirectional"))
    )
    (net (code "72") (name "unconnected-(M1-PB5-Pad14)") (class "Default")
      (node (ref "M1") (pin "14") (pinfunction "PB5_14") (pintype "bidirectional"))
    )
    (net (code "73") (name "unconnected-(M1-PB9-Pad13)") (class "Default")
      (node (ref "M1") (pin "13") (pinfunction "PB9_13") (pintype "bidirectional"))
    )
    (net (code "74") (name "unconnected-(M1-~{RST}-Pad3)") (class "Default")
      (node (ref "M1") (pin "3") (pinfunction "~{RST}_3") (pintype "input"))
    )
    (net (code "75") (name "unconnected-(M1-~{RST}-Pad28)") (class "Default")
      (node (ref "M1") (pin "28") (pinfunction "~{RST}_28") (pintype "input"))
    )
  )
)
